# POWER_SUPPLY.net
KiCad netlist of a schematic drawn in Altium Designer
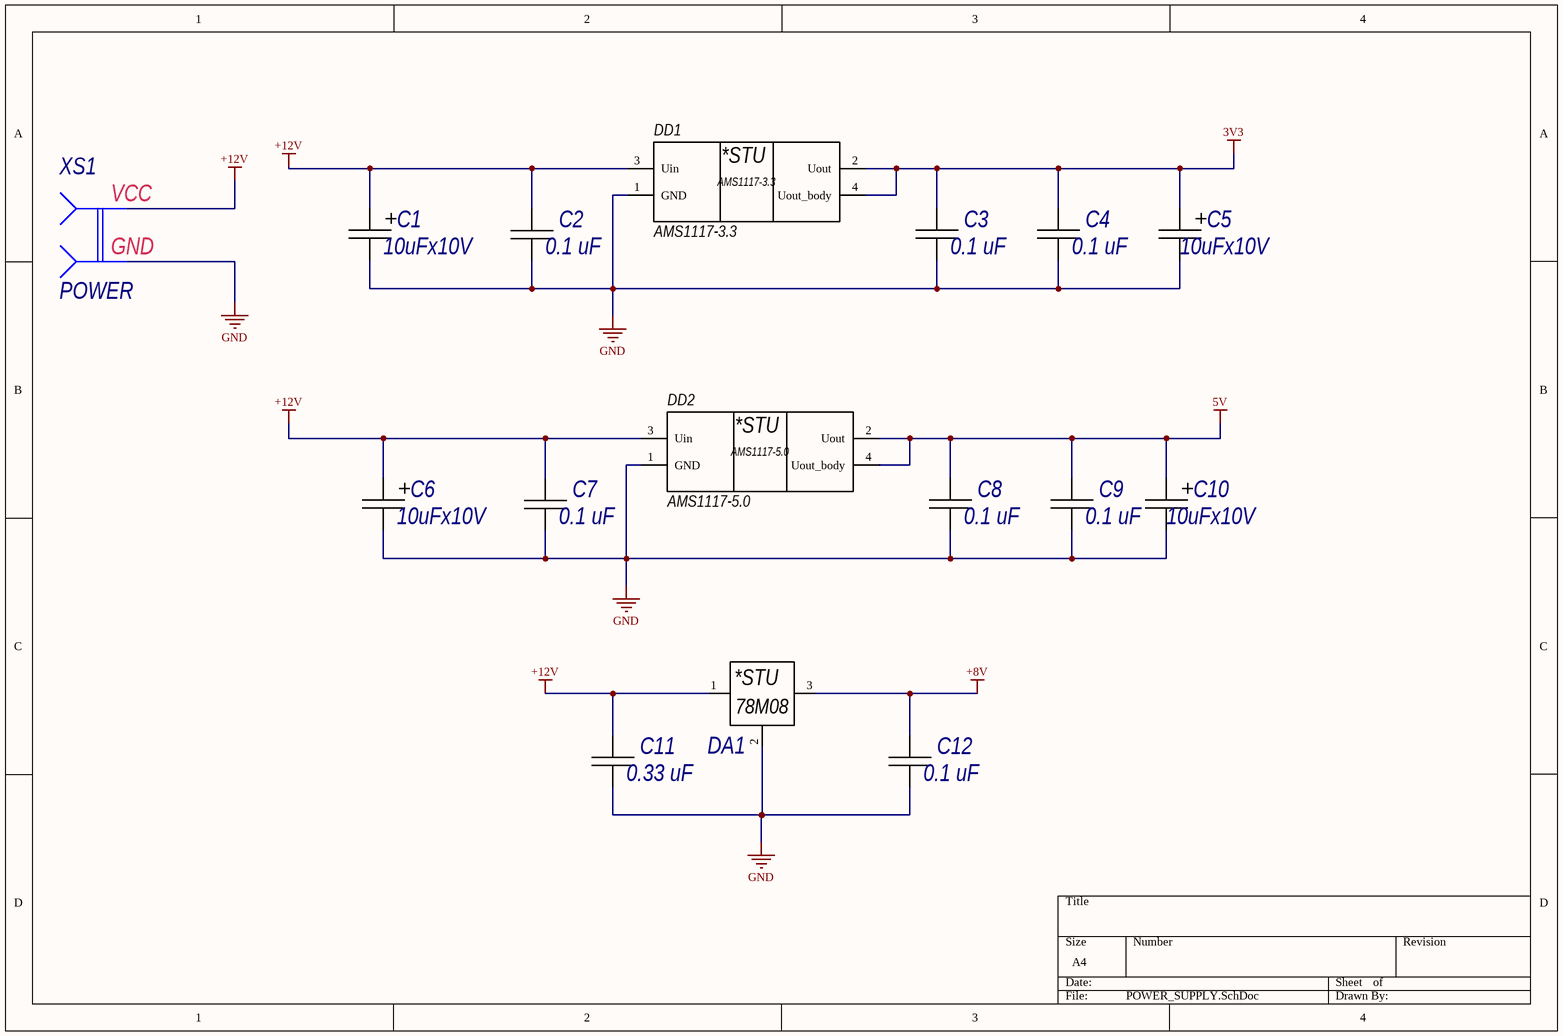
[diagram p0: POWER_SUPPLY.SchDoc]

(export (version "E")
  (design (tool "Eeschema 10.0.6"))
  (components
    (comp (ref "C1")
      (value "10uFx10V")
      (fields (field (name "PUBLISHER") "Andrew Danich"))
      (libsource (lib "PA_control_board") (part "CAP_TECAP_A"))
    )
    (comp (ref "C2")
      (value "0.1 uF")
      (footprint "C0805C")
      (fields (field (name "PUBLISHER") "Andrew Danich"))
      (libsource (lib "PA_control_board") (part "CAP_0805"))
    )
    (comp (ref "C3")
      (value "0.1 uF")
      (footprint "C0805C")
      (fields (field (name "PUBLISHER") "Andrew Danich"))
      (libsource (lib "PA_control_board") (part "CAP_0805"))
    )
    (comp (ref "C4")
      (value "0.1 uF")
      (footprint "C0805C")
      (fields (field (name "PUBLISHER") "Andrew Danich"))
      (libsource (lib "PA_control_board") (part "CAP_0805"))
    )
    (comp (ref "C5")
      (value "10uFx10V")
      (footprint "TECAP_D")
      (fields (field (name "PUBLISHER") "Andrew Danich"))
      (libsource (lib "PA_control_board") (part "CAP_TECAP_A"))
    )
    (comp (ref "C6")
      (value "10uFx10V")
      (fields (field (name "PUBLISHER") "Andrew Danich"))
      (libsource (lib "PA_control_board") (part "CAP_TECAP_A"))
    )
    (comp (ref "C7")
      (value "0.1 uF")
      (footprint "C0805C")
      (fields (field (name "PUBLISHER") "Andrew Danich"))
      (libsource (lib "PA_control_board") (part "CAP_0805"))
    )
    (comp (ref "C8")
      (value "0.1 uF")
      (footprint "C0805C")
      (fields (field (name "PUBLISHER") "Andrew Danich"))
      (libsource (lib "PA_control_board") (part "CAP_0805"))
    )
    (comp (ref "C9")
      (value "0.1 uF")
      (footprint "C0805C")
      (fields (field (name "PUBLISHER") "Andrew Danich"))
      (libsource (lib "PA_control_board") (part "CAP_0805"))
    )
    (comp (ref "C10")
      (value "10uFx10V")
      (footprint "TECAP_D")
      (fields (field (name "PUBLISHER") "Andrew Danich"))
      (libsource (lib "PA_control_board") (part "CAP_TECAP_A"))
    )
    (comp (ref "C11")
      (value "0.33 uF")
      (footprint "C0805C")
      (fields (field (name "PUBLISHER") "Andrew Danich"))
      (libsource (lib "PA_control_board") (part "CAP_0805"))
    )
    (comp (ref "C12")
      (value "0.1 uF")
      (footprint "C0805C")
      (fields (field (name "PUBLISHER") "Andrew Danich"))
      (libsource (lib "PA_control_board") (part "CAP_0805"))
    )
    (comp (ref "DA1")
      (value "78M08CDT")
      (footprint "SC_TO-252AA")
      (fields (field (name "PUBLISHER") "Andrew Danich"))
      (libsource (lib "PA_control_board") (part "78M08CDT"))
    )
    (comp (ref "DD1")
      (value "AMS1117-3.3")
      (footprint "SOT229P700X180-4N")
      (description "Sot223/Pkg 1-Amp 3.3-Volt Low Drop Out Voltage Regulatator")
      (fields (field (name "MF") "Advanced Monolithic Systems"))
      (libsource (lib "PA_control_board") (part "AMS1117-3.3"))
    )
    (comp (ref "DD2")
      (value "AMS1117-5.0")
      (footprint "SOT229P700X180-4N")
      (description "Sot223/Pkg 1-Amp 3.3-Volt Low Drop Out Voltage Regulatator")
      (fields (field (name "MP") "AMS1117-3.3") (field (name "MF") "Advanced Monolithic Systems"))
      (libsource (lib "PA_control_board") (part "AMS1117-5.0"))
    )
    (comp (ref "XS1")
      (value "POWER")
      (footprint "DG25C-B-02P-13")
      (fields (field (name "PUBLISHER") "Andrew Danich"))
      (libsource (lib "PA_control_board") (part "CONNECT_PW"))
    )
  )
  (nets
    (net (code "1") (name "+8V") (class "Default")
      (node (ref "C12") (pin "2") (pinfunction "2_2") (pintype "passive"))
      (node (ref "DA1") (pin "3") (pinfunction "Out_3") (pintype "passive"))
    )
    (net (code "2") (name "+12V") (class "Default")
      (node (ref "C1") (pin "1") (pinfunction "1_1") (pintype "passive"))
      (node (ref "C11") (pin "2") (pinfunction "2_2") (pintype "passive"))
      (node (ref "C2") (pin "2") (pinfunction "2_2") (pintype "passive"))
      (node (ref "C6") (pin "1") (pinfunction "1_1") (pintype "passive"))
      (node (ref "C7") (pin "2") (pinfunction "2_2") (pintype "passive"))
      (node (ref "DA1") (pin "1") (pinfunction "In_1") (pintype "passive"))
      (node (ref "DD1") (pin "3") (pinfunction "Uin_3") (pintype "power_in"))
      (node (ref "DD2") (pin "3") (pinfunction "Uin_3") (pintype "power_in"))
      (node (ref "XS1") (pin "2") (pintype "passive"))
    )
    (net (code "3") (name "3V3") (class "Default")
      (node (ref "C3") (pin "2") (pinfunction "2_2") (pintype "passive"))
      (node (ref "C4") (pin "2") (pinfunction "2_2") (pintype "passive"))
      (node (ref "C5") (pin "1") (pinfunction "1_1") (pintype "passive"))
      (node (ref "DD1") (pin "2") (pinfunction "Uout_2") (pintype "power_in"))
      (node (ref "DD1") (pin "4") (pinfunction "Uout_body_4") (pintype "power_in"))
    )
    (net (code "4") (name "5V") (class "Default")
      (node (ref "C10") (pin "1") (pinfunction "1_1") (pintype "passive"))
      (node (ref "C8") (pin "2") (pinfunction "2_2") (pintype "passive"))
      (node (ref "C9") (pin "2") (pinfunction "2_2") (pintype "passive"))
      (node (ref "DD2") (pin "2") (pinfunction "Uout_2") (pintype "power_in"))
      (node (ref "DD2") (pin "4") (pinfunction "Uout_body_4") (pintype "power_in"))
    )
    (net (code "5") (name "GND") (class "Default")
      (node (ref "C1") (pin "2") (pinfunction "2_2") (pintype "passive"))
      (node (ref "C10") (pin "2") (pinfunction "2_2") (pintype "passive"))
      (node (ref "C11") (pin "1") (pinfunction "1_1") (pintype "passive"))
      (node (ref "C12") (pin "1") (pinfunction "1_1") (pintype "passive"))
      (node (ref "C2") (pin "1") (pinfunction "1_1") (pintype "passive"))
      (node (ref "C3") (pin "1") (pinfunction "1_1") (pintype "passive"))
      (node (ref "C4") (pin "1") (pinfunction "1_1") (pintype "passive"))
      (node (ref "C5") (pin "2") (pinfunction "2_2") (pintype "passive"))
      (node (ref "C6") (pin "2") (pinfunction "2_2") (pintype "passive"))
      (node (ref "C7") (pin "1") (pinfunction "1_1") (pintype "passive"))
      (node (ref "C8") (pin "1") (pinfunction "1_1") (pintype "passive"))
      (node (ref "C9") (pin "1") (pinfunction "1_1") (pintype "passive"))
      (node (ref "DA1") (pin "2") (pinfunction "GND_2") (pintype "passive"))
      (node (ref "DD1") (pin "1") (pinfunction "GND_1") (pintype "passive"))
      (node (ref "DD2") (pin "1") (pinfunction "GND_1") (pintype "passive"))
      (node (ref "XS1") (pin "1") (pintype "passive"))
    )
  )
)
